# Agit_POVera_rev_5.net
KiCad netlist of a schematic drawn in EAGLE
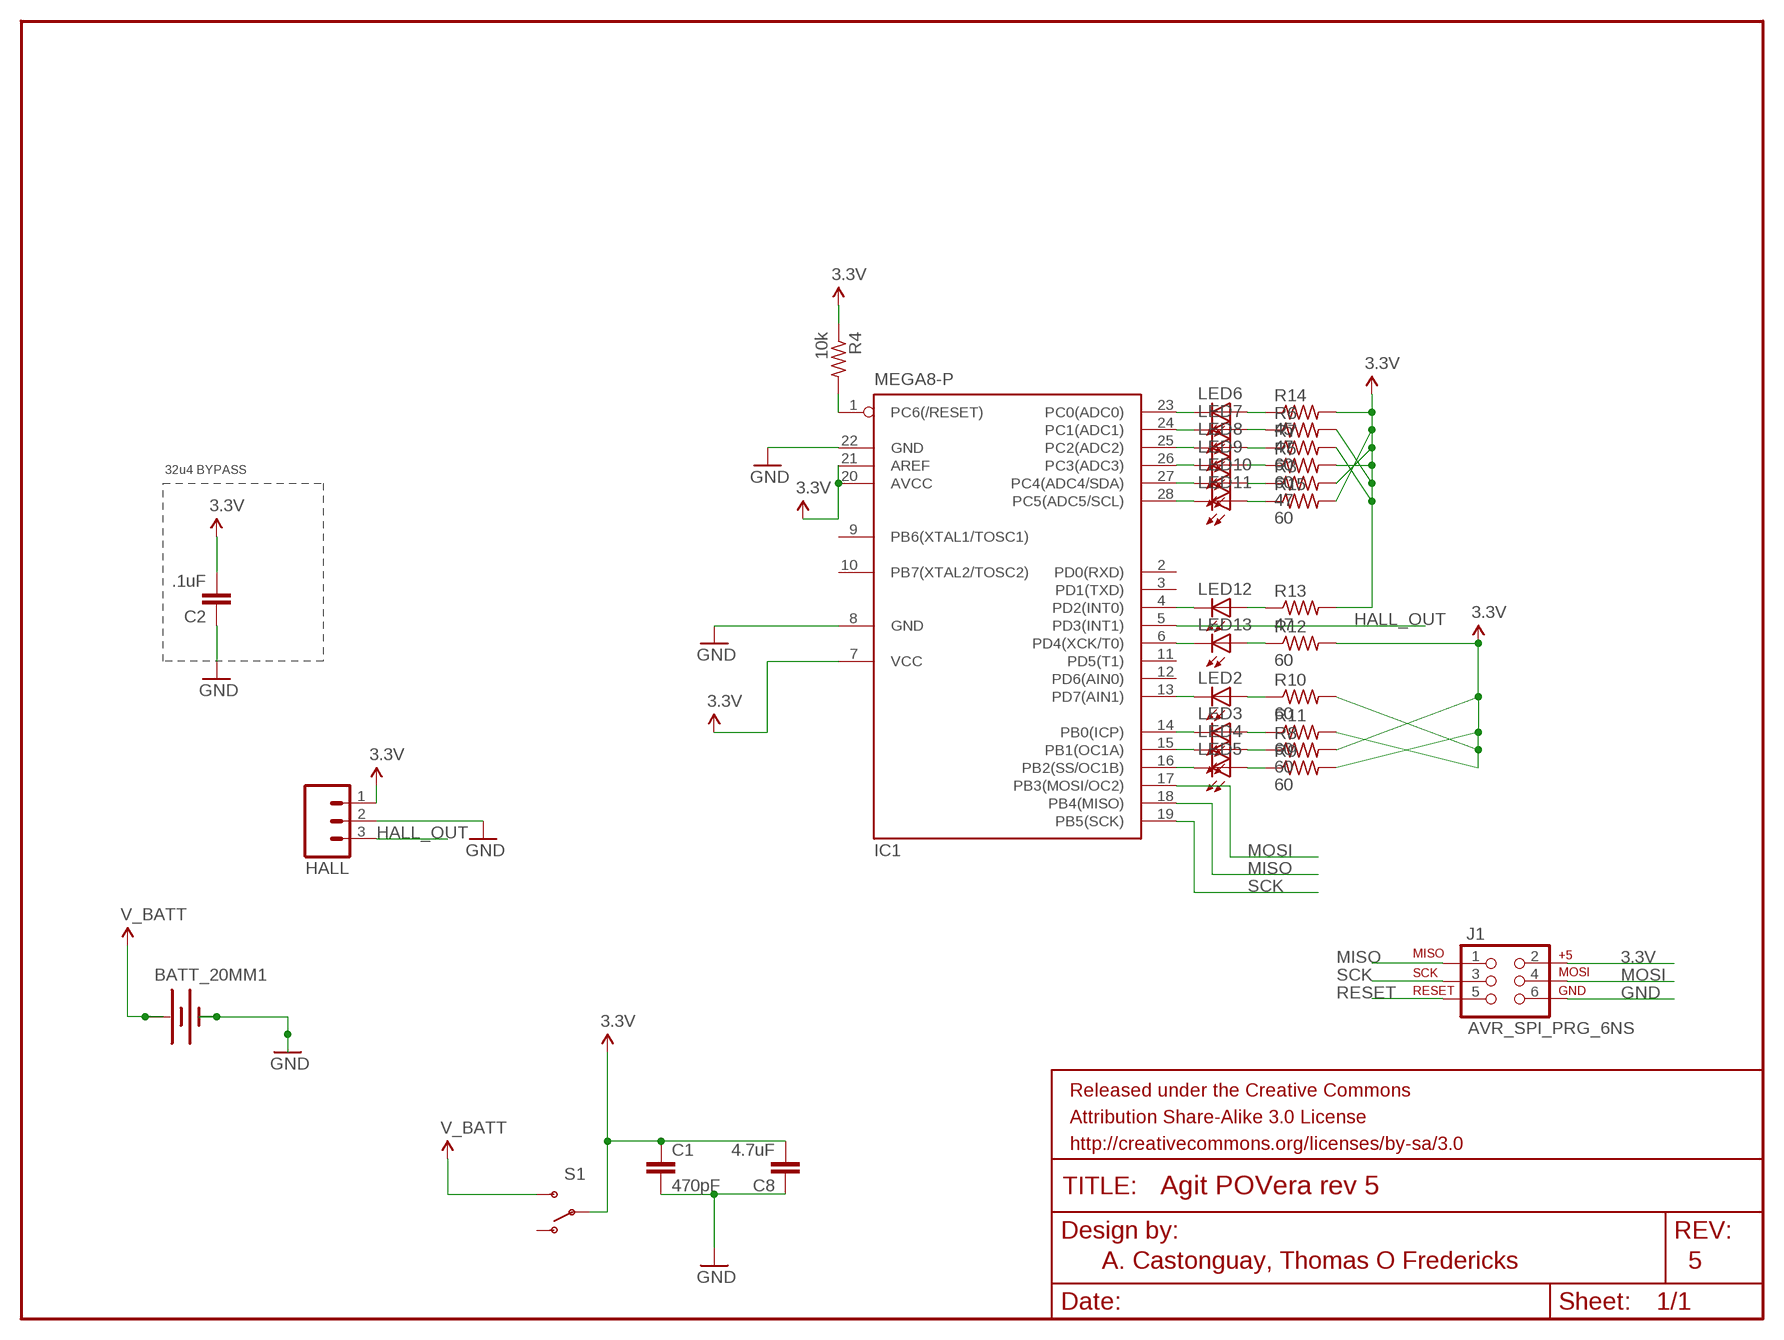
[diagram p0: schematic, sheet 1]

(export (version "E")
  (design (tool "Eeschema 10.0.6"))
  (components
    (comp (ref "BATT_20MM1")
      (value "BATTERIE")
      (footprint "eagle-import:BATTERIE")
      (libsource (lib "eagle-import") (part "BATTERIE"))
    )
    (comp (ref "C1")
      (value "470pF")
      (footprint "eagle-import:CAP-PTH-SMALLEZ")
      (libsource (lib "eagle-import") (part "CAPEZ"))
    )
    (comp (ref "C2")
      (value ".1uF")
      (footprint "eagle-import:CAP-PTH-SMALLEZ")
      (libsource (lib "eagle-import") (part "CAPEZ"))
    )
    (comp (ref "C8")
      (value "4.7uF")
      (footprint "eagle-import:CAP-PTH-SMALLEZ")
      (libsource (lib "eagle-import") (part "CAPEZ"))
    )
    (comp (ref "HALL")
      (value "M03PTH")
      (footprint "eagle-import:1X03")
      (libsource (lib "eagle-import") (part "M03PTH"))
    )
    (comp (ref "IC1")
      (value "MEGA8-P")
      (footprint "eagle-import:DIL28-3")
      (libsource (lib "eagle-import") (part "MEGA8-P"))
    )
    (comp (ref "J1")
      (value "AVR_SPI_PRG_6NS")
      (footprint "eagle-import:2X3-NS")
      (libsource (lib "eagle-import") (part "AVR_SPI_PRG_6NS"))
    )
    (comp (ref "LED2")
      (value "LED5MM")
      (footprint "eagle-import:LED5MM")
      (libsource (lib "eagle-import") (part "LED5MM"))
    )
    (comp (ref "LED3")
      (value "LED5MM")
      (footprint "eagle-import:LED5MM")
      (libsource (lib "eagle-import") (part "LED5MM"))
    )
    (comp (ref "LED4")
      (value "LED5MM")
      (footprint "eagle-import:LED5MM")
      (libsource (lib "eagle-import") (part "LED5MM"))
    )
    (comp (ref "LED5")
      (value "LED5MM")
      (footprint "eagle-import:LED5MM")
      (libsource (lib "eagle-import") (part "LED5MM"))
    )
    (comp (ref "LED6")
      (value "LED5MM")
      (footprint "eagle-import:LED5MM")
      (libsource (lib "eagle-import") (part "LED5MM"))
    )
    (comp (ref "LED7")
      (value "LED5MM")
      (footprint "eagle-import:LED5MM")
      (libsource (lib "eagle-import") (part "LED5MM"))
    )
    (comp (ref "LED8")
      (value "LED5MM")
      (footprint "eagle-import:LED5MM")
      (libsource (lib "eagle-import") (part "LED5MM"))
    )
    (comp (ref "LED9")
      (value "LED5MM")
      (footprint "eagle-import:LED5MM")
      (libsource (lib "eagle-import") (part "LED5MM"))
    )
    (comp (ref "LED10")
      (value "LED5MM")
      (footprint "eagle-import:LED5MM")
      (libsource (lib "eagle-import") (part "LED5MM"))
    )
    (comp (ref "LED11")
      (value "LED5MM")
      (footprint "eagle-import:LED5MM")
      (libsource (lib "eagle-import") (part "LED5MM"))
    )
    (comp (ref "LED12")
      (value "LED5MM")
      (footprint "eagle-import:LED5MM")
      (libsource (lib "eagle-import") (part "LED5MM"))
    )
    (comp (ref "LED13")
      (value "LED5MM")
      (footprint "eagle-import:LED5MM")
      (libsource (lib "eagle-import") (part "LED5MM"))
    )
    (comp (ref "R3")
      (value "47")
      (footprint "eagle-import:0204_7")
      (libsource (lib "eagle-import") (part "R-US_0204/7"))
    )
    (comp (ref "R4")
      (value "10k")
      (footprint "eagle-import:0204_7")
      (libsource (lib "eagle-import") (part "R-US_0204/7"))
    )
    (comp (ref "R5")
      (value "60")
      (footprint "eagle-import:0204_7")
      (libsource (lib "eagle-import") (part "R-US_0204/7"))
    )
    (comp (ref "R6")
      (value "47")
      (footprint "eagle-import:0204_7")
      (libsource (lib "eagle-import") (part "R-US_0204/7"))
    )
    (comp (ref "R7")
      (value "60")
      (footprint "eagle-import:0204_7")
      (libsource (lib "eagle-import") (part "R-US_0204/7"))
    )
    (comp (ref "R8")
      (value "60")
      (footprint "eagle-import:0204_7")
      (libsource (lib "eagle-import") (part "R-US_0204/7"))
    )
    (comp (ref "R9")
      (value "60")
      (footprint "eagle-import:0204_7")
      (libsource (lib "eagle-import") (part "R-US_0204/7"))
    )
    (comp (ref "R10")
      (value "60")
      (footprint "eagle-import:0204_7")
      (libsource (lib "eagle-import") (part "R-US_0204/7"))
    )
    (comp (ref "R11")
      (value "60")
      (footprint "eagle-import:0204_7")
      (libsource (lib "eagle-import") (part "R-US_0204/7"))
    )
    (comp (ref "R12")
      (value "60")
      (footprint "eagle-import:0204_7")
      (libsource (lib "eagle-import") (part "R-US_0204/7"))
    )
    (comp (ref "R13")
      (value "47")
      (footprint "eagle-import:0204_7")
      (libsource (lib "eagle-import") (part "R-US_0204/7"))
    )
    (comp (ref "R14")
      (value "45")
      (footprint "eagle-import:0204_7")
      (libsource (lib "eagle-import") (part "R-US_0204/7"))
    )
    (comp (ref "R15")
      (value "60")
      (footprint "eagle-import:0204_7")
      (libsource (lib "eagle-import") (part "R-US_0204/7"))
    )
    (comp (ref "S1")
      (value "SWITCH-SPDTPTH")
      (footprint "eagle-import:SWITCH-SPDT")
      (libsource (lib "eagle-import") (part "SWITCH-SPDTPTH"))
    )
  )
  (nets
    (net (code "1") (name "/HALL_OUT") (class "Default")
      (node (ref "HALL") (pin "3") (pinfunction "3_3") (pintype "passive"))
      (node (ref "IC1") (pin "5") (pinfunction "PD3(INT1)_5") (pintype "bidirectional"))
    )
    (net (code "2") (name "/MISO") (class "Default")
      (node (ref "IC1") (pin "18") (pinfunction "PB4(MISO)_18") (pintype "bidirectional"))
      (node (ref "J1") (pin "1") (pinfunction "1_1") (pintype "passive"))
    )
    (net (code "3") (name "/MOSI") (class "Default")
      (node (ref "IC1") (pin "17") (pinfunction "PB3(MOSI/OC2)_17") (pintype "bidirectional"))
      (node (ref "J1") (pin "4") (pinfunction "4_4") (pintype "passive"))
    )
    (net (code "4") (name "/RESET") (class "Default")
      (node (ref "IC1") (pin "1") (pinfunction "PC6(/RESET)_1") (pintype "bidirectional"))
      (node (ref "J1") (pin "5") (pinfunction "5_5") (pintype "passive"))
      (node (ref "R4") (pin "2") (pinfunction "2_2") (pintype "passive"))
    )
    (net (code "5") (name "/SCK") (class "Default")
      (node (ref "IC1") (pin "19") (pinfunction "PB5(SCK)_19") (pintype "bidirectional"))
      (node (ref "J1") (pin "3") (pinfunction "3_3") (pintype "passive"))
    )
    (net (code "6") (name "3.3V") (class "Default")
      (node (ref "C1") (pin "1") (pinfunction "1_1") (pintype "passive"))
      (node (ref "C2") (pin "2") (pinfunction "2_2") (pintype "passive"))
      (node (ref "C8") (pin "2") (pinfunction "2_2") (pintype "passive"))
      (node (ref "HALL") (pin "1") (pinfunction "1_1") (pintype "passive"))
      (node (ref "IC1") (pin "20") (pinfunction "AVCC_20") (pintype "power_in"))
      (node (ref "IC1") (pin "21") (pinfunction "AREF_21") (pintype "passive"))
      (node (ref "IC1") (pin "7") (pinfunction "VCC_7") (pintype "power_in"))
      (node (ref "J1") (pin "2") (pinfunction "2_2") (pintype "passive"))
      (node (ref "R10") (pin "2") (pinfunction "2_2") (pintype "passive"))
      (node (ref "R11") (pin "2") (pinfunction "2_2") (pintype "passive"))
      (node (ref "R12") (pin "2") (pinfunction "2_2") (pintype "passive"))
      (node (ref "R13") (pin "2") (pinfunction "2_2") (pintype "passive"))
      (node (ref "R14") (pin "2") (pinfunction "2_2") (pintype "passive"))
      (node (ref "R15") (pin "2") (pinfunction "2_2") (pintype "passive"))
      (node (ref "R3") (pin "2") (pinfunction "2_2") (pintype "passive"))
      (node (ref "R4") (pin "1") (pinfunction "1_1") (pintype "passive"))
      (node (ref "R5") (pin "2") (pinfunction "2_2") (pintype "passive"))
      (node (ref "R6") (pin "2") (pinfunction "2_2") (pintype "passive"))
      (node (ref "R7") (pin "2") (pinfunction "2_2") (pintype "passive"))
      (node (ref "R8") (pin "2") (pinfunction "2_2") (pintype "passive"))
      (node (ref "R9") (pin "2") (pinfunction "2_2") (pintype "passive"))
      (node (ref "S1") (pin "2") (pinfunction "P_2") (pintype "passive"))
    )
    (net (code "7") (name "GND") (class "Default")
      (node (ref "BATT_20MM1") (pin "2") (pinfunction "-_2") (pintype "power_in"))
      (node (ref "C1") (pin "2") (pinfunction "2_2") (pintype "passive"))
      (node (ref "C2") (pin "1") (pinfunction "1_1") (pintype "passive"))
      (node (ref "C8") (pin "1") (pinfunction "1_1") (pintype "passive"))
      (node (ref "HALL") (pin "2") (pinfunction "2_2") (pintype "passive"))
      (node (ref "IC1") (pin "22") (pinfunction "GND_22") (pintype "power_in"))
      (node (ref "IC1") (pin "8") (pinfunction "GND_8") (pintype "power_in"))
      (node (ref "J1") (pin "6") (pinfunction "6_6") (pintype "passive"))
    )
    (net (code "8") (name "Net-(IC1-PB0(ICP))") (class "Default")
      (node (ref "IC1") (pin "14") (pinfunction "PB0(ICP)_14") (pintype "bidirectional"))
      (node (ref "LED3") (pin "K") (pinfunction "C_K") (pintype "passive"))
    )
    (net (code "9") (name "Net-(IC1-PB1(OC1A))") (class "Default")
      (node (ref "IC1") (pin "15") (pinfunction "PB1(OC1A)_15") (pintype "bidirectional"))
      (node (ref "LED4") (pin "K") (pinfunction "C_K") (pintype "passive"))
    )
    (net (code "10") (name "Net-(IC1-PB2(SS{slash}OC1B))") (class "Default")
      (node (ref "IC1") (pin "16") (pinfunction "PB2(SS/OC1B)_16") (pintype "bidirectional"))
      (node (ref "LED5") (pin "K") (pinfunction "C_K") (pintype "passive"))
    )
    (net (code "11") (name "Net-(IC1-PC0(ADC0))") (class "Default")
      (node (ref "IC1") (pin "23") (pinfunction "PC0(ADC0)_23") (pintype "bidirectional"))
      (node (ref "LED6") (pin "K") (pinfunction "C_K") (pintype "passive"))
    )
    (net (code "12") (name "Net-(IC1-PC1(ADC1))") (class "Default")
      (node (ref "IC1") (pin "24") (pinfunction "PC1(ADC1)_24") (pintype "bidirectional"))
      (node (ref "LED7") (pin "K") (pinfunction "C_K") (pintype "passive"))
    )
    (net (code "13") (name "Net-(IC1-PC2(ADC2))") (class "Default")
      (node (ref "IC1") (pin "25") (pinfunction "PC2(ADC2)_25") (pintype "bidirectional"))
      (node (ref "LED8") (pin "K") (pinfunction "C_K") (pintype "passive"))
    )
    (net (code "14") (name "Net-(IC1-PC3(ADC3))") (class "Default")
      (node (ref "IC1") (pin "26") (pinfunction "PC3(ADC3)_26") (pintype "bidirectional"))
      (node (ref "LED9") (pin "K") (pinfunction "C_K") (pintype "passive"))
    )
    (net (code "15") (name "Net-(IC1-PC4(ADC4{slash}SDA))") (class "Default")
      (node (ref "IC1") (pin "27") (pinfunction "PC4(ADC4/SDA)_27") (pintype "bidirectional"))
      (node (ref "LED10") (pin "K") (pinfunction "C_K") (pintype "passive"))
    )
    (net (code "16") (name "Net-(IC1-PC5(ADC5{slash}SCL))") (class "Default")
      (node (ref "IC1") (pin "28") (pinfunction "PC5(ADC5/SCL)_28") (pintype "bidirectional"))
      (node (ref "LED11") (pin "K") (pinfunction "C_K") (pintype "passive"))
    )
    (net (code "17") (name "Net-(IC1-PD2(INT0))") (class "Default")
      (node (ref "IC1") (pin "4") (pinfunction "PD2(INT0)_4") (pintype "bidirectional"))
      (node (ref "LED12") (pin "K") (pinfunction "C_K") (pintype "passive"))
    )
    (net (code "18") (name "Net-(IC1-PD4(XCK{slash}T0))") (class "Default")
      (node (ref "IC1") (pin "6") (pinfunction "PD4(XCK/T0)_6") (pintype "bidirectional"))
      (node (ref "LED13") (pin "K") (pinfunction "C_K") (pintype "passive"))
    )
    (net (code "19") (name "Net-(IC1-PD7(AIN1))") (class "Default")
      (node (ref "IC1") (pin "13") (pinfunction "PD7(AIN1)_13") (pintype "bidirectional"))
      (node (ref "LED2") (pin "K") (pinfunction "C_K") (pintype "passive"))
    )
    (net (code "20") (name "Net-(LED2-PadA)") (class "Default")
      (node (ref "LED2") (pin "A") (pinfunction "A_A") (pintype "passive"))
      (node (ref "R10") (pin "1") (pinfunction "1_1") (pintype "passive"))
    )
    (net (code "21") (name "Net-(LED3-PadA)") (class "Default")
      (node (ref "LED3") (pin "A") (pinfunction "A_A") (pintype "passive"))
      (node (ref "R11") (pin "1") (pinfunction "1_1") (pintype "passive"))
    )
    (net (code "22") (name "Net-(LED4-PadA)") (class "Default")
      (node (ref "LED4") (pin "A") (pinfunction "A_A") (pintype "passive"))
      (node (ref "R8") (pin "1") (pinfunction "1_1") (pintype "passive"))
    )
    (net (code "23") (name "Net-(LED5-PadA)") (class "Default")
      (node (ref "LED5") (pin "A") (pinfunction "A_A") (pintype "passive"))
      (node (ref "R9") (pin "1") (pinfunction "1_1") (pintype "passive"))
    )
    (net (code "24") (name "Net-(LED6-PadA)") (class "Default")
      (node (ref "LED6") (pin "A") (pinfunction "A_A") (pintype "passive"))
      (node (ref "R14") (pin "1") (pinfunction "1_1") (pintype "passive"))
    )
    (net (code "25") (name "Net-(LED7-PadA)") (class "Default")
      (node (ref "LED7") (pin "A") (pinfunction "A_A") (pintype "passive"))
      (node (ref "R6") (pin "1") (pinfunction "1_1") (pintype "passive"))
    )
    (net (code "26") (name "Net-(LED8-PadA)") (class "Default")
      (node (ref "LED8") (pin "A") (pinfunction "A_A") (pintype "passive"))
      (node (ref "R7") (pin "1") (pinfunction "1_1") (pintype "passive"))
    )
    (net (code "27") (name "Net-(LED9-PadA)") (class "Default")
      (node (ref "LED9") (pin "A") (pinfunction "A_A") (pintype "passive"))
      (node (ref "R5") (pin "1") (pinfunction "1_1") (pintype "passive"))
    )
    (net (code "28") (name "Net-(LED10-PadA)") (class "Default")
      (node (ref "LED10") (pin "A") (pinfunction "A_A") (pintype "passive"))
      (node (ref "R3") (pin "1") (pinfunction "1_1") (pintype "passive"))
    )
    (net (code "29") (name "Net-(LED11-PadA)") (class "Default")
      (node (ref "LED11") (pin "A") (pinfunction "A_A") (pintype "passive"))
      (node (ref "R15") (pin "1") (pinfunction "1_1") (pintype "passive"))
    )
    (net (code "30") (name "Net-(LED12-PadA)") (class "Default")
      (node (ref "LED12") (pin "A") (pinfunction "A_A") (pintype "passive"))
      (node (ref "R13") (pin "1") (pinfunction "1_1") (pintype "passive"))
    )
    (net (code "31") (name "Net-(LED13-PadA)") (class "Default")
      (node (ref "LED13") (pin "A") (pinfunction "A_A") (pintype "passive"))
      (node (ref "R12") (pin "1") (pinfunction "1_1") (pintype "passive"))
    )
    (net (code "32") (name "V_BATT") (class "Default")
      (node (ref "BATT_20MM1") (pin "1") (pinfunction "+_1") (pintype "power_in"))
      (node (ref "S1") (pin "3") (pinfunction "S_3") (pintype "passive"))
    )
    (net (code "33") (name "unconnected-(IC1-PB6(XTAL1{slash}TOSC1)-Pad9)") (class "Default")
      (node (ref "IC1") (pin "9") (pinfunction "PB6(XTAL1/TOSC1)_9") (pintype "bidirectional"))
    )
    (net (code "34") (name "unconnected-(IC1-PB7(XTAL2{slash}TOSC2)-Pad10)") (class "Default")
      (node (ref "IC1") (pin "10") (pinfunction "PB7(XTAL2/TOSC2)_10") (pintype "bidirectional"))
    )
    (net (code "35") (name "unconnected-(IC1-PD0(RXD)-Pad2)") (class "Default")
      (node (ref "IC1") (pin "2") (pinfunction "PD0(RXD)_2") (pintype "bidirectional"))
    )
    (net (code "36") (name "unconnected-(IC1-PD1(TXD)-Pad3)") (class "Default")
      (node (ref "IC1") (pin "3") (pinfunction "PD1(TXD)_3") (pintype "bidirectional"))
    )
    (net (code "37") (name "unconnected-(IC1-PD5(T1)-Pad11)") (class "Default")
      (node (ref "IC1") (pin "11") (pinfunction "PD5(T1)_11") (pintype "bidirectional"))
    )
    (net (code "38") (name "unconnected-(IC1-PD6(AIN0)-Pad12)") (class "Default")
      (node (ref "IC1") (pin "12") (pinfunction "PD6(AIN0)_12") (pintype "bidirectional"))
    )
    (net (code "39") (name "unconnected-(S1-O-Pad1)") (class "Default")
      (node (ref "S1") (pin "1") (pinfunction "O_1") (pintype "passive"))
    )
  )
)
